# 04_-_BOTTON.net
KiCad netlist of a schematic drawn in Altium Designer
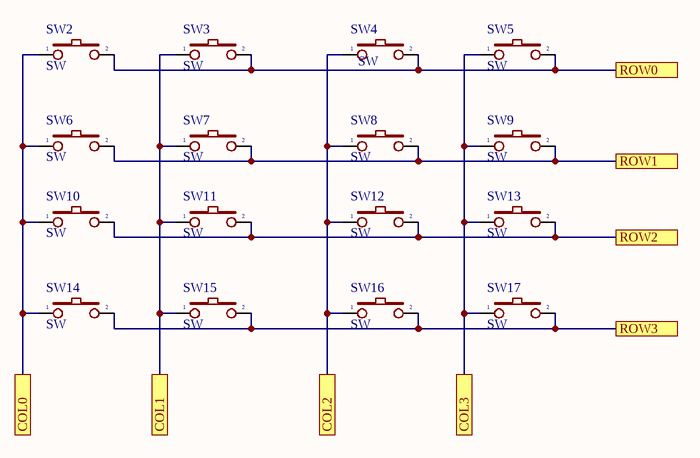
[diagram p0: [04] - BOTTON.SchDoc]

(export (version "E")
  (design (tool "Eeschema 10.0.6"))
  (components
    (comp (ref "SW2")
      (value "SW")
      (footprint "SW2")
      (description "Switch button 2 pin")
      (libsource (lib "My Library") (part "SW2"))
    )
    (comp (ref "SW3")
      (value "SW")
      (footprint "SW2")
      (description "Switch button 2 pin")
      (libsource (lib "My Library") (part "SW2"))
    )
    (comp (ref "SW4")
      (value "SW")
      (footprint "SW2")
      (description "Switch button 2 pin")
      (libsource (lib "My Library") (part "SW2"))
    )
    (comp (ref "SW5")
      (value "SW")
      (footprint "SW2")
      (description "Switch button 2 pin")
      (libsource (lib "My Library") (part "SW2"))
    )
    (comp (ref "SW6")
      (value "SW")
      (footprint "SW2")
      (description "Switch button 2 pin")
      (libsource (lib "My Library") (part "SW2"))
    )
    (comp (ref "SW7")
      (value "SW")
      (footprint "SW2")
      (description "Switch button 2 pin")
      (libsource (lib "My Library") (part "SW2"))
    )
    (comp (ref "SW8")
      (value "SW")
      (footprint "SW2")
      (description "Switch button 2 pin")
      (libsource (lib "My Library") (part "SW2"))
    )
    (comp (ref "SW9")
      (value "SW")
      (footprint "SW2")
      (description "Switch button 2 pin")
      (libsource (lib "My Library") (part "SW2"))
    )
    (comp (ref "SW10")
      (value "SW")
      (footprint "SW2")
      (description "Switch button 2 pin")
      (libsource (lib "My Library") (part "SW2"))
    )
    (comp (ref "SW11")
      (value "SW")
      (footprint "SW2")
      (description "Switch button 2 pin")
      (libsource (lib "My Library") (part "SW2"))
    )
    (comp (ref "SW12")
      (value "SW")
      (footprint "SW2")
      (description "Switch button 2 pin")
      (libsource (lib "My Library") (part "SW2"))
    )
    (comp (ref "SW13")
      (value "SW")
      (footprint "SW2")
      (description "Switch button 2 pin")
      (libsource (lib "My Library") (part "SW2"))
    )
    (comp (ref "SW14")
      (value "SW")
      (footprint "SW2")
      (description "Switch button 2 pin")
      (libsource (lib "My Library") (part "SW2"))
    )
    (comp (ref "SW15")
      (value "SW")
      (footprint "SW2")
      (description "Switch button 2 pin")
      (libsource (lib "My Library") (part "SW2"))
    )
    (comp (ref "SW16")
      (value "SW")
      (footprint "SW2")
      (description "Switch button 2 pin")
      (libsource (lib "My Library") (part "SW2"))
    )
    (comp (ref "SW17")
      (value "SW")
      (footprint "SW2")
      (description "Switch button 2 pin")
      (libsource (lib "My Library") (part "SW2"))
    )
  )
  (nets
    (net (code "1") (name "/COL0") (class "Default")
      (node (ref "SW10") (pin "1") (pinfunction "1_1") (pintype "passive"))
      (node (ref "SW14") (pin "1") (pinfunction "1_1") (pintype "passive"))
      (node (ref "SW2") (pin "1") (pinfunction "1_1") (pintype "passive"))
      (node (ref "SW6") (pin "1") (pinfunction "1_1") (pintype "passive"))
    )
    (net (code "2") (name "/COL1") (class "Default")
      (node (ref "SW11") (pin "1") (pinfunction "1_1") (pintype "passive"))
      (node (ref "SW15") (pin "1") (pinfunction "1_1") (pintype "passive"))
      (node (ref "SW3") (pin "1") (pinfunction "1_1") (pintype "passive"))
      (node (ref "SW7") (pin "1") (pinfunction "1_1") (pintype "passive"))
    )
    (net (code "3") (name "/COL2") (class "Default")
      (node (ref "SW12") (pin "1") (pinfunction "1_1") (pintype "passive"))
      (node (ref "SW16") (pin "1") (pinfunction "1_1") (pintype "passive"))
      (node (ref "SW4") (pin "1") (pinfunction "1_1") (pintype "passive"))
      (node (ref "SW8") (pin "1") (pinfunction "1_1") (pintype "passive"))
    )
    (net (code "4") (name "/COL3") (class "Default")
      (node (ref "SW13") (pin "1") (pinfunction "1_1") (pintype "passive"))
      (node (ref "SW17") (pin "1") (pinfunction "1_1") (pintype "passive"))
      (node (ref "SW5") (pin "1") (pinfunction "1_1") (pintype "passive"))
      (node (ref "SW9") (pin "1") (pinfunction "1_1") (pintype "passive"))
    )
    (net (code "5") (name "/ROW0") (class "Default")
      (node (ref "SW2") (pin "2") (pinfunction "2_2") (pintype "passive"))
      (node (ref "SW3") (pin "2") (pinfunction "2_2") (pintype "passive"))
      (node (ref "SW4") (pin "2") (pinfunction "2_2") (pintype "passive"))
      (node (ref "SW5") (pin "2") (pinfunction "2_2") (pintype "passive"))
    )
    (net (code "6") (name "/ROW1") (class "Default")
      (node (ref "SW6") (pin "2") (pinfunction "2_2") (pintype "passive"))
      (node (ref "SW7") (pin "2") (pinfunction "2_2") (pintype "passive"))
      (node (ref "SW8") (pin "2") (pinfunction "2_2") (pintype "passive"))
      (node (ref "SW9") (pin "2") (pinfunction "2_2") (pintype "passive"))
    )
    (net (code "7") (name "/ROW2") (class "Default")
      (node (ref "SW10") (pin "2") (pinfunction "2_2") (pintype "passive"))
      (node (ref "SW11") (pin "2") (pinfunction "2_2") (pintype "passive"))
      (node (ref "SW12") (pin "2") (pinfunction "2_2") (pintype "passive"))
      (node (ref "SW13") (pin "2") (pinfunction "2_2") (pintype "passive"))
    )
    (net (code "8") (name "/ROW3") (class "Default")
      (node (ref "SW14") (pin "2") (pinfunction "2_2") (pintype "passive"))
      (node (ref "SW15") (pin "2") (pinfunction "2_2") (pintype "passive"))
      (node (ref "SW16") (pin "2") (pinfunction "2_2") (pintype "passive"))
      (node (ref "SW17") (pin "2") (pinfunction "2_2") (pintype "passive"))
    )
  )
)
